# Dummy_load_2__4-30V_0-4_25A__v2_0.net
KiCad netlist of a schematic drawn in EAGLE
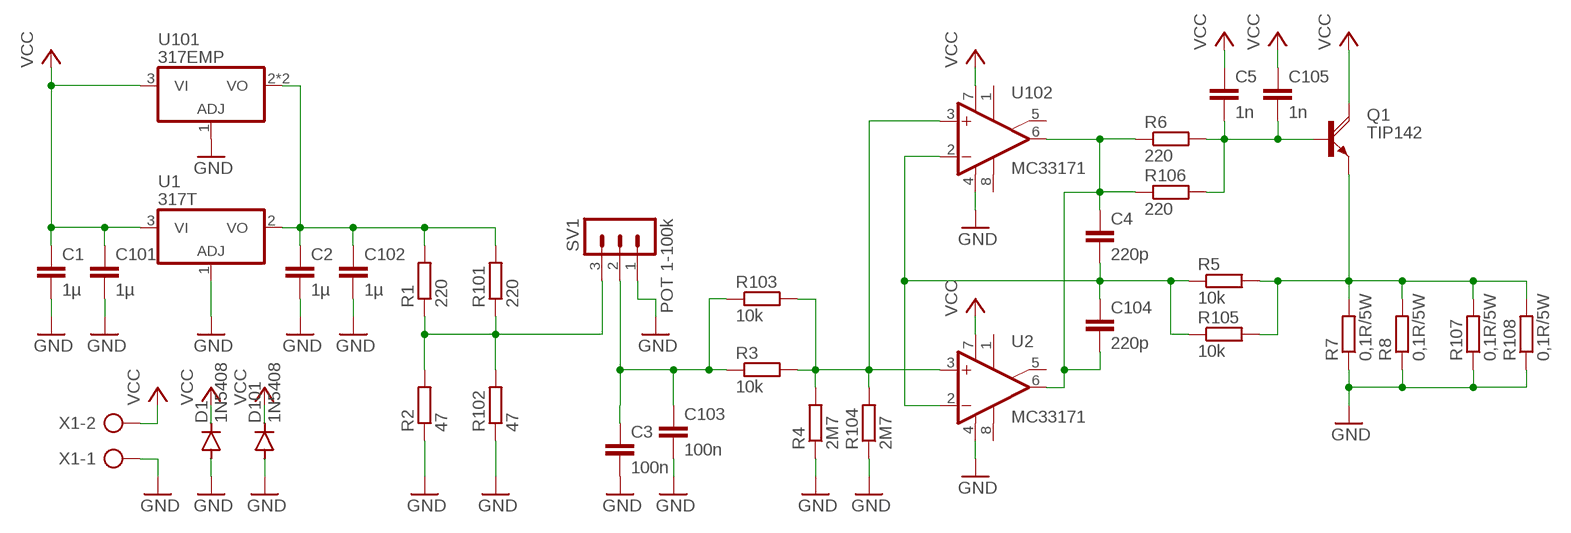
[diagram p0: schematic, sheet 1]

(export (version "E")
  (design (tool "Eeschema 10.0.6"))
  (components
    (comp (ref "C1")
      (value "1µ")
      (footprint "eagle-import:C050-024X044")
      (libsource (lib "eagle-import") (part "C-EU050-024X044"))
    )
    (comp (ref "C2")
      (value "1µ")
      (footprint "eagle-import:C050-024X044")
      (libsource (lib "eagle-import") (part "C-EU050-024X044"))
    )
    (comp (ref "C3")
      (value "100n")
      (footprint "eagle-import:C050-024X044")
      (libsource (lib "eagle-import") (part "C-EU050-024X044"))
    )
    (comp (ref "C4")
      (value "220p")
      (footprint "eagle-import:C050-024X044")
      (libsource (lib "eagle-import") (part "C-EU050-024X044"))
    )
    (comp (ref "C5")
      (value "1n")
      (footprint "eagle-import:C050-024X044")
      (libsource (lib "eagle-import") (part "C-EU050-024X044"))
    )
    (comp (ref "C101")
      (value "1µ")
      (footprint "eagle-import:C1206")
      (libsource (lib "eagle-import") (part "C-EUC1206"))
    )
    (comp (ref "C102")
      (value "1µ")
      (footprint "eagle-import:C1206")
      (libsource (lib "eagle-import") (part "C-EUC1206"))
    )
    (comp (ref "C103")
      (value "100n")
      (footprint "eagle-import:C1206")
      (libsource (lib "eagle-import") (part "C-EUC1206"))
    )
    (comp (ref "C104")
      (value "220p")
      (footprint "eagle-import:C1206")
      (libsource (lib "eagle-import") (part "C-EUC1206"))
    )
    (comp (ref "C105")
      (value "1n")
      (footprint "eagle-import:C1206")
      (libsource (lib "eagle-import") (part "C-EUC1206"))
    )
    (comp (ref "D1")
      (value "1N5408")
      (footprint "eagle-import:C1702-06")
      (libsource (lib "eagle-import") (part "DIODE-C1702-06"))
    )
    (comp (ref "D101")
      (value "1N5408")
      (footprint "eagle-import:DO214AA")
      (libsource (lib "eagle-import") (part "DIODE-DO214AA"))
    )
    (comp (ref "Q1")
      (value "TIP142")
      (footprint "eagle-import:SOT93V")
      (libsource (lib "eagle-import") (part "TIP142VERTICAL"))
    )
    (comp (ref "R1")
      (value "220")
      (footprint "eagle-import:0207_10")
      (libsource (lib "eagle-import") (part "R-EU_0207/10"))
    )
    (comp (ref "R2")
      (value "47")
      (footprint "eagle-import:0207_10")
      (libsource (lib "eagle-import") (part "R-EU_0207/10"))
    )
    (comp (ref "R3")
      (value "10k")
      (footprint "eagle-import:0207_10")
      (libsource (lib "eagle-import") (part "R-EU_0207/10"))
    )
    (comp (ref "R4")
      (value "2M7")
      (footprint "eagle-import:0207_10")
      (libsource (lib "eagle-import") (part "R-EU_0207/10"))
    )
    (comp (ref "R5")
      (value "10k")
      (footprint "eagle-import:0207_10")
      (libsource (lib "eagle-import") (part "R-EU_0207/10"))
    )
    (comp (ref "R6")
      (value "220")
      (footprint "eagle-import:0207_10")
      (libsource (lib "eagle-import") (part "R-EU_0207/10"))
    )
    (comp (ref "R7")
      (value "0,1R/5W")
      (footprint "eagle-import:VTA53")
      (libsource (lib "eagle-import") (part "R-EU_VTA53"))
    )
    (comp (ref "R8")
      (value "0,1R/5W")
      (footprint "eagle-import:VTA53")
      (libsource (lib "eagle-import") (part "R-EU_VTA53"))
    )
    (comp (ref "R101")
      (value "220")
      (footprint "eagle-import:R1206")
      (libsource (lib "eagle-import") (part "R-EU_R1206"))
    )
    (comp (ref "R102")
      (value "47")
      (footprint "eagle-import:R1206")
      (libsource (lib "eagle-import") (part "R-EU_R1206"))
    )
    (comp (ref "R103")
      (value "10k")
      (footprint "eagle-import:R1206")
      (libsource (lib "eagle-import") (part "R-EU_R1206"))
    )
    (comp (ref "R104")
      (value "2M7")
      (footprint "eagle-import:R1206")
      (libsource (lib "eagle-import") (part "R-EU_R1206"))
    )
    (comp (ref "R105")
      (value "10k")
      (footprint "eagle-import:R1206")
      (libsource (lib "eagle-import") (part "R-EU_R1206"))
    )
    (comp (ref "R106")
      (value "220")
      (footprint "eagle-import:R1206")
      (libsource (lib "eagle-import") (part "R-EU_R1206"))
    )
    (comp (ref "R107")
      (value "0,1R/5W")
      (footprint "eagle-import:P0817V")
      (libsource (lib "eagle-import") (part "R-EU_0817/7V"))
    )
    (comp (ref "R108")
      (value "0,1R/5W")
      (footprint "eagle-import:P0817V")
      (libsource (lib "eagle-import") (part "R-EU_0817/7V"))
    )
    (comp (ref "SV1")
      (value "POT 1-100k")
      (footprint "eagle-import:MA03-1")
      (libsource (lib "eagle-import") (part "MA03-1"))
    )
    (comp (ref "U1")
      (value "317T")
      (footprint "eagle-import:TO220H")
      (libsource (lib "eagle-import") (part "317T"))
    )
    (comp (ref "U2")
      (value "MC33171")
      (footprint "eagle-import:DIL08")
      (libsource (lib "eagle-import") (part "741PLM"))
    )
    (comp (ref "U101")
      (value "317EMP")
      (footprint "eagle-import:SOT223")
      (libsource (lib "eagle-import") (part "317EMP"))
    )
    (comp (ref "U102")
      (value "MC33171")
      (footprint "eagle-import:SO08")
      (libsource (lib "eagle-import") (part "741DLM"))
    )
    (comp (ref "X1")
      (value "AK500/2")
      (footprint "eagle-import:AK500_2")
      (libsource (lib "eagle-import") (part "AK500/2"))
    )
  )
  (nets
    (net (code "1") (name "GND") (class "Default")
      (node (ref "C1") (pin "2") (pinfunction "2_2") (pintype "passive"))
      (node (ref "C101") (pin "2") (pinfunction "2_2") (pintype "passive"))
      (node (ref "C102") (pin "2") (pinfunction "2_2") (pintype "passive"))
      (node (ref "C103") (pin "2") (pinfunction "2_2") (pintype "passive"))
      (node (ref "C2") (pin "2") (pinfunction "2_2") (pintype "passive"))
      (node (ref "C3") (pin "2") (pinfunction "2_2") (pintype "passive"))
      (node (ref "D1") (pin "A") (pinfunction "A_A") (pintype "passive"))
      (node (ref "D101") (pin "A") (pinfunction "A_A") (pintype "passive"))
      (node (ref "R102") (pin "1") (pinfunction "1_1") (pintype "passive"))
      (node (ref "R104") (pin "1") (pinfunction "1_1") (pintype "passive"))
      (node (ref "R107") (pin "1") (pinfunction "1_1") (pintype "passive"))
      (node (ref "R108") (pin "1") (pinfunction "1_1") (pintype "passive"))
      (node (ref "R2") (pin "1") (pinfunction "1_1") (pintype "passive"))
      (node (ref "R4") (pin "1") (pinfunction "1_1") (pintype "passive"))
      (node (ref "R7") (pin "1") (pinfunction "1_1") (pintype "passive"))
      (node (ref "R8") (pin "1") (pinfunction "1_1") (pintype "passive"))
      (node (ref "SV1") (pin "1") (pinfunction "1_1") (pintype "passive"))
      (node (ref "U1") (pin "1") (pinfunction "ADJ_1") (pintype "input"))
      (node (ref "U101") (pin "1") (pinfunction "ADJ_1") (pintype "input"))
      (node (ref "U102") (pin "4") (pinfunction "V-_4") (pintype "power_in"))
      (node (ref "U2") (pin "4") (pinfunction "V-_4") (pintype "power_in"))
      (node (ref "X1") (pin "1") (pinfunction "KL_1") (pintype "passive"))
    )
    (net (code "2") (name "Net-(C103-Pad1)") (class "Default")
      (node (ref "C103") (pin "1") (pinfunction "1_1") (pintype "passive"))
      (node (ref "C3") (pin "1") (pinfunction "1_1") (pintype "passive"))
      (node (ref "R103") (pin "1") (pinfunction "1_1") (pintype "passive"))
      (node (ref "R3") (pin "1") (pinfunction "1_1") (pintype "passive"))
      (node (ref "SV1") (pin "2") (pinfunction "2_2") (pintype "passive"))
    )
    (net (code "3") (name "Net-(C105-Pad2)") (class "Default")
      (node (ref "C105") (pin "2") (pinfunction "2_2") (pintype "passive"))
      (node (ref "C5") (pin "2") (pinfunction "2_2") (pintype "passive"))
      (node (ref "Q1") (pin "B") (pinfunction "B_B") (pintype "passive"))
      (node (ref "R106") (pin "2") (pinfunction "2_2") (pintype "passive"))
      (node (ref "R6") (pin "2") (pinfunction "2_2") (pintype "passive"))
    )
    (net (code "4") (name "Net-(Q1-PadE)") (class "Default")
      (node (ref "Q1") (pin "E") (pinfunction "E_E") (pintype "passive"))
      (node (ref "R105") (pin "2") (pinfunction "2_2") (pintype "passive"))
      (node (ref "R107") (pin "2") (pinfunction "2_2") (pintype "passive"))
      (node (ref "R108") (pin "2") (pinfunction "2_2") (pintype "passive"))
      (node (ref "R5") (pin "2") (pinfunction "2_2") (pintype "passive"))
      (node (ref "R7") (pin "2") (pinfunction "2_2") (pintype "passive"))
      (node (ref "R8") (pin "2") (pinfunction "2_2") (pintype "passive"))
    )
    (net (code "5") (name "Net-(R1-Pad1)") (class "Default")
      (node (ref "R1") (pin "1") (pinfunction "1_1") (pintype "passive"))
      (node (ref "R101") (pin "1") (pinfunction "1_1") (pintype "passive"))
      (node (ref "R102") (pin "2") (pinfunction "2_2") (pintype "passive"))
      (node (ref "R2") (pin "2") (pinfunction "2_2") (pintype "passive"))
      (node (ref "SV1") (pin "3") (pinfunction "3_3") (pintype "passive"))
    )
    (net (code "6") (name "Net-(U1-VO)") (class "Default")
      (node (ref "C102") (pin "1") (pinfunction "1_1") (pintype "passive"))
      (node (ref "C2") (pin "1") (pinfunction "1_1") (pintype "passive"))
      (node (ref "R1") (pin "2") (pinfunction "2_2") (pintype "passive"))
      (node (ref "R101") (pin "2") (pinfunction "2_2") (pintype "passive"))
      (node (ref "U1") (pin "2") (pinfunction "VO_2") (pintype "passive"))
      (node (ref "U101") (pin "2") (pinfunction "VO_2") (pintype "passive"))
      (node (ref "U101") (pin "4") (pinfunction "VO_4") (pintype "passive"))
    )
    (net (code "7") (name "Net-(U102-+IN)") (class "Default")
      (node (ref "R103") (pin "2") (pinfunction "2_2") (pintype "passive"))
      (node (ref "R104") (pin "2") (pinfunction "2_2") (pintype "passive"))
      (node (ref "R3") (pin "2") (pinfunction "2_2") (pintype "passive"))
      (node (ref "R4") (pin "2") (pinfunction "2_2") (pintype "passive"))
      (node (ref "U102") (pin "3") (pinfunction "+IN_3") (pintype "input"))
      (node (ref "U2") (pin "3") (pinfunction "+IN_3") (pintype "input"))
    )
    (net (code "8") (name "Net-(U102--IN)") (class "Default")
      (node (ref "C104") (pin "1") (pinfunction "1_1") (pintype "passive"))
      (node (ref "C4") (pin "2") (pinfunction "2_2") (pintype "passive"))
      (node (ref "R105") (pin "1") (pinfunction "1_1") (pintype "passive"))
      (node (ref "R5") (pin "1") (pinfunction "1_1") (pintype "passive"))
      (node (ref "U102") (pin "2") (pinfunction "-IN_2") (pintype "input"))
      (node (ref "U2") (pin "2") (pinfunction "-IN_2") (pintype "input"))
    )
    (net (code "9") (name "Net-(U102-OUT)") (class "Default")
      (node (ref "C104") (pin "2") (pinfunction "2_2") (pintype "passive"))
      (node (ref "C4") (pin "1") (pinfunction "1_1") (pintype "passive"))
      (node (ref "R106") (pin "1") (pinfunction "1_1") (pintype "passive"))
      (node (ref "R6") (pin "1") (pinfunction "1_1") (pintype "passive"))
      (node (ref "U102") (pin "6") (pinfunction "OUT_6") (pintype "output"))
      (node (ref "U2") (pin "6") (pinfunction "OUT_6") (pintype "output"))
    )
    (net (code "10") (name "VCC") (class "Default")
      (node (ref "C1") (pin "1") (pinfunction "1_1") (pintype "passive"))
      (node (ref "C101") (pin "1") (pinfunction "1_1") (pintype "passive"))
      (node (ref "C105") (pin "1") (pinfunction "1_1") (pintype "passive"))
      (node (ref "C5") (pin "1") (pinfunction "1_1") (pintype "passive"))
      (node (ref "D1") (pin "C") (pinfunction "C_C") (pintype "passive"))
      (node (ref "D101") (pin "C") (pinfunction "C_C") (pintype "passive"))
      (node (ref "Q1") (pin "C") (pinfunction "C_C") (pintype "passive"))
      (node (ref "U1") (pin "3") (pinfunction "VI_3") (pintype "input"))
      (node (ref "U101") (pin "3") (pinfunction "VI_3") (pintype "input"))
      (node (ref "U102") (pin "7") (pinfunction "V+_7") (pintype "power_in"))
      (node (ref "U2") (pin "7") (pinfunction "V+_7") (pintype "power_in"))
      (node (ref "X1") (pin "2") (pinfunction "KL_2") (pintype "passive"))
    )
    (net (code "11") (name "unconnected-(U2-ON1-Pad1)") (class "Default")
      (node (ref "U2") (pin "1") (pinfunction "ON1_1") (pintype "passive"))
    )
    (net (code "12") (name "unconnected-(U2-ON2-Pad5)") (class "Default")
      (node (ref "U2") (pin "5") (pinfunction "ON2_5") (pintype "passive"))
    )
    (net (code "13") (name "unconnected-(U2-OPT-Pad8)") (class "Default")
      (node (ref "U2") (pin "8") (pinfunction "OPT_8") (pintype "passive"))
    )
    (net (code "14") (name "unconnected-(U102-ON1-Pad1)") (class "Default")
      (node (ref "U102") (pin "1") (pinfunction "ON1_1") (pintype "passive"))
    )
    (net (code "15") (name "unconnected-(U102-ON2-Pad5)") (class "Default")
      (node (ref "U102") (pin "5") (pinfunction "ON2_5") (pintype "passive"))
    )
    (net (code "16") (name "unconnected-(U102-OPT-Pad8)") (class "Default")
      (node (ref "U102") (pin "8") (pinfunction "OPT_8") (pintype "passive"))
    )
  )
)
